# KeyboardMoudle1.net
KiCad netlist of a schematic drawn in Altium Designer
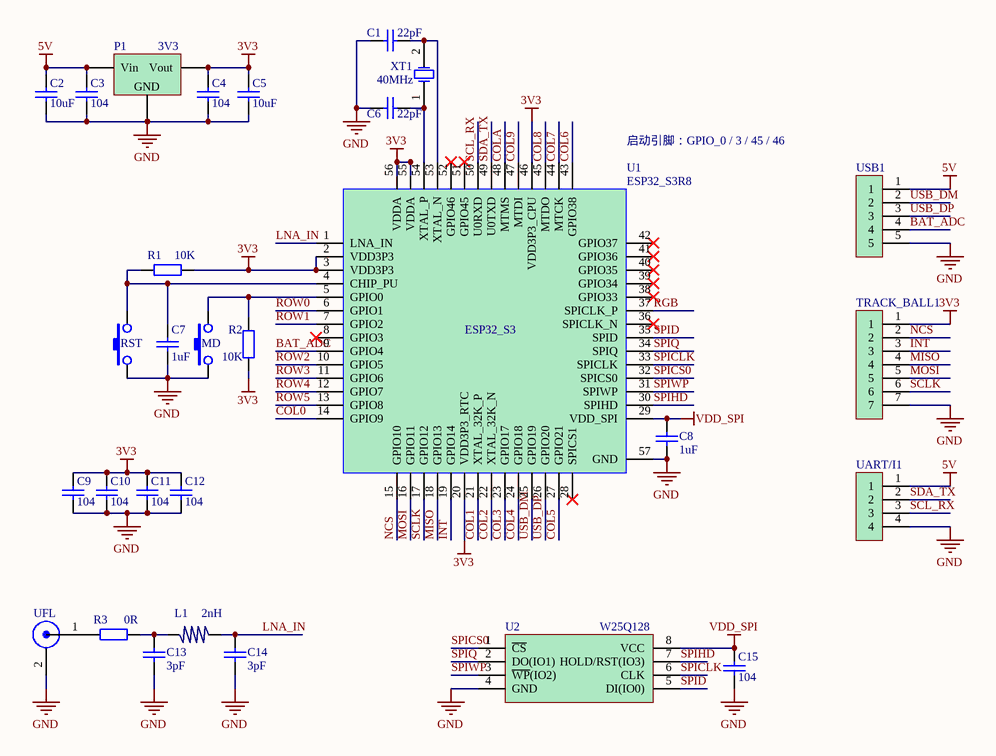
[diagram p0: KeyboardMoudle1.SchDoc]

(export (version "E")
  (design (tool "Eeschema 10.0.6"))
  (components
    (comp (ref "C1")
      (value "22pF")
      (footprint "0603")
      (description "贴片电容 0603")
      (libsource (lib "MT_Device") (part "CAP_0603"))
    )
    (comp (ref "C2")
      (value "10uF")
      (footprint "0603")
      (description "贴片电容 0603")
      (libsource (lib "MT_Device") (part "CAP_0603"))
    )
    (comp (ref "C3")
      (value "104")
      (footprint "0603")
      (description "贴片电容 0603")
      (libsource (lib "MT_Device") (part "CAP_0603"))
    )
    (comp (ref "C4")
      (value "104")
      (footprint "0603")
      (description "贴片电容 0603")
      (libsource (lib "MT_Device") (part "CAP_0603"))
    )
    (comp (ref "C5")
      (value "10uF")
      (footprint "0603")
      (description "贴片电容 0603")
      (libsource (lib "MT_Device") (part "CAP_0603"))
    )
    (comp (ref "C6")
      (value "22pF")
      (footprint "0603")
      (description "贴片电容 0603")
      (libsource (lib "MT_Device") (part "CAP_0603"))
    )
    (comp (ref "C7")
      (value "1uF")
      (footprint "0603")
      (description "贴片电容 0603")
      (libsource (lib "MT_Device") (part "CAP_0603"))
    )
    (comp (ref "C8")
      (value "1uF")
      (footprint "0603")
      (description "贴片电容 0603")
      (libsource (lib "MT_Device") (part "CAP_0603"))
    )
    (comp (ref "C9")
      (value "104")
      (footprint "0603")
      (description "贴片电容 0603")
      (libsource (lib "MT_Device") (part "CAP_0603"))
    )
    (comp (ref "C10")
      (value "104")
      (footprint "0603")
      (description "贴片电容 0603")
      (libsource (lib "MT_Device") (part "CAP_0603"))
    )
    (comp (ref "C11")
      (value "104")
      (footprint "0603")
      (description "贴片电容 0603")
      (libsource (lib "MT_Device") (part "CAP_0603"))
    )
    (comp (ref "C12")
      (value "104")
      (footprint "0603")
      (description "贴片电容 0603")
      (libsource (lib "MT_Device") (part "CAP_0603"))
    )
    (comp (ref "C13")
      (value "3pF")
      (footprint "0603")
      (description "贴片电容 0603")
      (libsource (lib "MT_Device") (part "CAP_0603"))
    )
    (comp (ref "C14")
      (value "3pF")
      (footprint "0603")
      (description "贴片电容 0603")
      (libsource (lib "MT_Device") (part "CAP_0603"))
    )
    (comp (ref "C15")
      (value "104")
      (footprint "0603")
      (description "贴片电容 0603")
      (libsource (lib "MT_Device") (part "CAP_0603"))
    )
    (comp (ref "L1")
      (value "2nH")
      (footprint "0603")
      (description "电感 0603")
      (libsource (lib "MT_Device") (part "L_0603"))
    )
    (comp (ref "MD")
      (value "KEY")
      (footprint "KEY_SMT_4_L")
      (description "卧式贴片按键 2*4*3.5mm")
      (libsource (lib "MT_Device") (part "KEY_SMT_4_L"))
    )
    (comp (ref "P1")
      (value "3V3")
      (footprint "SOT223")
      (description "线性稳压器")
      (libsource (lib "MT_Device") (part "LDO_AMS1117"))
    )
    (comp (ref "R1")
      (value "10K")
      (footprint "R_0603")
      (description "电阻 0603")
      (libsource (lib "") (part "RES_0603_1"))
    )
    (comp (ref "R2")
      (value "10K")
      (footprint "R_0603")
      (description "电阻 0603")
      (libsource (lib "") (part "RES_0603_2"))
    )
    (comp (ref "R3")
      (value "0R")
      (footprint "R_0603")
      (description "电阻 0603")
      (libsource (lib "MT_Device") (part "RES_0603"))
    )
    (comp (ref "RST")
      (value "KEY")
      (footprint "KEY_SMT_4_L")
      (description "卧式贴片按键 2*4*3.5mm")
      (libsource (lib "MT_Device") (part "KEY_SMT_4_L"))
    )
    (comp (ref "TRACK_BALL1")
      (value "SH1.25mm_7P")
      (footprint "SH1.25MM_7P")
      (libsource (lib "MT_Connector") (part "SH1.25mm_7P"))
    )
    (comp (ref "U1")
      (value "ESP32_S3R8")
      (footprint "QFN56")
      (description "ESP32")
      (libsource (lib "MT_Chip") (part "ESP32_S3"))
    )
    (comp (ref "U2")
      (value "W25Q128")
      (footprint "SOIC8-208MIL")
      (description "FLASH")
      (libsource (lib "MT_Chip") (part "W25Q64"))
    )
    (comp (ref "UART/I1")
      (value "SH1.25mm_4P")
      (footprint "SH1.25MM_4P")
      (libsource (lib "MT_Connector") (part "SH1.25mm_4P"))
    )
    (comp (ref "UFL")
      (value "UFL")
      (footprint "IPEX")
      (description "射频接口")
      (libsource (lib "MT_Device") (part "UFL"))
    )
    (comp (ref "USB1")
      (value "SH1.25mm_5P")
      (footprint "SH1.25MM_5P")
      (libsource (lib "MT_Connector") (part "SH1.25mm_5P"))
    )
    (comp (ref "XT1")
      (value "40MHz")
      (footprint "XTAL_5032")
      (description "贴片无源晶振")
      (libsource (lib "MT_Device") (part "XTAL_5032"))
    )
  )
  (nets
    (net (code "1") (name "/BAT_ADC") (class "Default")
      (node (ref "U1") (pin "9") (pinfunction "GPIO4_9") (pintype "passive"))
      (node (ref "USB1") (pin "4") (pinfunction "4_4") (pintype "passive"))
    )
    (net (code "2") (name "/COL0") (class "Default")
      (node (ref "U1") (pin "14") (pinfunction "GPIO9_14") (pintype "passive"))
    )
    (net (code "3") (name "/COL1") (class "Default")
      (node (ref "U1") (pin "21") (pinfunction "XTAL_32K_P_21") (pintype "passive"))
    )
    (net (code "4") (name "/COL2") (class "Default")
      (node (ref "U1") (pin "22") (pinfunction "XTAL_32K_N_22") (pintype "passive"))
    )
    (net (code "5") (name "/COL3") (class "Default")
      (node (ref "U1") (pin "23") (pinfunction "GPIO17_23") (pintype "passive"))
    )
    (net (code "6") (name "/COL4") (class "Default")
      (node (ref "U1") (pin "24") (pinfunction "GPIO18_24") (pintype "passive"))
    )
    (net (code "7") (name "/COL5") (class "Default")
      (node (ref "U1") (pin "27") (pinfunction "GPIO21_27") (pintype "passive"))
    )
    (net (code "8") (name "/COL6") (class "Default")
      (node (ref "U1") (pin "43") (pinfunction "GPIO38_43") (pintype "passive"))
    )
    (net (code "9") (name "/COL7") (class "Default")
      (node (ref "U1") (pin "44") (pinfunction "MTCK_44") (pintype "passive"))
    )
    (net (code "10") (name "/COL8") (class "Default")
      (node (ref "U1") (pin "45") (pinfunction "MTDO_45") (pintype "passive"))
    )
    (net (code "11") (name "/COL9") (class "Default")
      (node (ref "U1") (pin "47") (pinfunction "MTDI_47") (pintype "passive"))
    )
    (net (code "12") (name "/COLA") (class "Default")
      (node (ref "U1") (pin "48") (pinfunction "MTMS_48") (pintype "passive"))
    )
    (net (code "13") (name "/INT") (class "Default")
      (node (ref "TRACK_BALL1") (pin "3") (pinfunction "3_3") (pintype "passive"))
      (node (ref "U1") (pin "19") (pinfunction "GPIO14_19") (pintype "passive"))
    )
    (net (code "14") (name "/LNA_IN") (class "Default")
      (node (ref "C14") (pin "1") (pinfunction "1_1") (pintype "passive"))
      (node (ref "L1") (pin "2") (pintype "passive"))
      (node (ref "U1") (pin "1") (pinfunction "LNA_IN_1") (pintype "passive"))
    )
    (net (code "15") (name "/MISO") (class "Default")
      (node (ref "TRACK_BALL1") (pin "4") (pinfunction "4_4") (pintype "passive"))
      (node (ref "U1") (pin "18") (pinfunction "GPIO13_18") (pintype "passive"))
    )
    (net (code "16") (name "/MOSI") (class "Default")
      (node (ref "TRACK_BALL1") (pin "5") (pinfunction "5_5") (pintype "passive"))
      (node (ref "U1") (pin "16") (pinfunction "GPIO11_16") (pintype "passive"))
    )
    (net (code "17") (name "/NCS") (class "Default")
      (node (ref "TRACK_BALL1") (pin "2") (pinfunction "2_2") (pintype "passive"))
      (node (ref "U1") (pin "15") (pinfunction "GPIO10_15") (pintype "passive"))
    )
    (net (code "18") (name "/RGB") (class "Default")
      (node (ref "U1") (pin "37") (pinfunction "SPICLK_P_37") (pintype "passive"))
    )
    (net (code "19") (name "/ROW0") (class "Default")
      (node (ref "U1") (pin "6") (pinfunction "GPIO1_6") (pintype "passive"))
    )
    (net (code "20") (name "/ROW1") (class "Default")
      (node (ref "U1") (pin "7") (pinfunction "GPIO2_7") (pintype "passive"))
    )
    (net (code "21") (name "/ROW2") (class "Default")
      (node (ref "U1") (pin "10") (pinfunction "GPIO5_10") (pintype "passive"))
    )
    (net (code "22") (name "/ROW3") (class "Default")
      (node (ref "U1") (pin "11") (pinfunction "GPIO6_11") (pintype "passive"))
    )
    (net (code "23") (name "/ROW4") (class "Default")
      (node (ref "U1") (pin "12") (pinfunction "GPIO7_12") (pintype "passive"))
    )
    (net (code "24") (name "/ROW5") (class "Default")
      (node (ref "U1") (pin "13") (pinfunction "GPIO8_13") (pintype "passive"))
    )
    (net (code "25") (name "/SCLK") (class "Default")
      (node (ref "TRACK_BALL1") (pin "6") (pinfunction "6_6") (pintype "passive"))
      (node (ref "U1") (pin "17") (pinfunction "GPIO12_17") (pintype "passive"))
    )
    (net (code "26") (name "/SCL_RX") (class "Default")
      (node (ref "U1") (pin "50") (pinfunction "U0RXD_50") (pintype "passive"))
      (node (ref "UART/I1") (pin "3") (pinfunction "3_3") (pintype "passive"))
    )
    (net (code "27") (name "/SDA_TX") (class "Default")
      (node (ref "U1") (pin "49") (pinfunction "U0TXD_49") (pintype "passive"))
      (node (ref "UART/I1") (pin "2") (pinfunction "2_2") (pintype "passive"))
    )
    (net (code "28") (name "/SPICLK") (class "Default")
      (node (ref "U1") (pin "33") (pinfunction "SPICLK_33") (pintype "passive"))
      (node (ref "U2") (pin "6") (pinfunction "CLK_6") (pintype "passive"))
    )
    (net (code "29") (name "/SPICS0") (class "Default")
      (node (ref "U1") (pin "32") (pinfunction "SPICS0_32") (pintype "passive"))
      (node (ref "U2") (pin "1") (pinfunction "~{CS}_1") (pintype "passive"))
    )
    (net (code "30") (name "/SPID") (class "Default")
      (node (ref "U1") (pin "35") (pinfunction "SPID_35") (pintype "passive"))
      (node (ref "U2") (pin "5") (pinfunction "DI(IO0)_5") (pintype "power_in"))
    )
    (net (code "31") (name "/SPIHD") (class "Default")
      (node (ref "U1") (pin "30") (pinfunction "SPIHD_30") (pintype "passive"))
      (node (ref "U2") (pin "7") (pinfunction "HOLD/RST(IO3)_7") (pintype "power_in"))
    )
    (net (code "32") (name "/SPIQ") (class "Default")
      (node (ref "U1") (pin "34") (pinfunction "SPIQ_34") (pintype "passive"))
      (node (ref "U2") (pin "2") (pinfunction "DO(IO1)_2") (pintype "passive"))
    )
    (net (code "33") (name "/SPIWP") (class "Default")
      (node (ref "U1") (pin "31") (pinfunction "SPIWP_31") (pintype "passive"))
      (node (ref "U2") (pin "3") (pinfunction "~{WP}(IO2)_3") (pintype "passive"))
    )
    (net (code "34") (name "/USB_DM") (class "Default")
      (node (ref "U1") (pin "25") (pinfunction "GPIO19_25") (pintype "passive"))
      (node (ref "USB1") (pin "2") (pinfunction "2_2") (pintype "passive"))
    )
    (net (code "35") (name "/USB_DP") (class "Default")
      (node (ref "U1") (pin "26") (pinfunction "GPIO20_26") (pintype "passive"))
      (node (ref "USB1") (pin "3") (pinfunction "3_3") (pintype "passive"))
    )
    (net (code "36") (name "3V3") (class "Default")
      (node (ref "C10") (pin "2") (pinfunction "2_2") (pintype "passive"))
      (node (ref "C11") (pin "2") (pinfunction "2_2") (pintype "passive"))
      (node (ref "C12") (pin "2") (pinfunction "2_2") (pintype "passive"))
      (node (ref "C4") (pin "2") (pinfunction "2_2") (pintype "passive"))
      (node (ref "C5") (pin "2") (pinfunction "2_2") (pintype "passive"))
      (node (ref "C9") (pin "2") (pinfunction "2_2") (pintype "passive"))
      (node (ref "P1") (pin "2") (pinfunction "Vout_2") (pintype "passive"))
      (node (ref "R1") (pin "1") (pinfunction "1_1") (pintype "passive"))
      (node (ref "R2") (pin "1") (pinfunction "1_1") (pintype "passive"))
      (node (ref "TRACK_BALL1") (pin "1") (pinfunction "1_1") (pintype "passive"))
      (node (ref "U1") (pin "2") (pinfunction "VDD3P3_2") (pintype "passive"))
      (node (ref "U1") (pin "20") (pinfunction "VDD3P3_RTC_20") (pintype "passive"))
      (node (ref "U1") (pin "3") (pinfunction "VDD3P3_3") (pintype "passive"))
      (node (ref "U1") (pin "46") (pinfunction "VDD3P3_CPU_46") (pintype "passive"))
      (node (ref "U1") (pin "55") (pinfunction "VDDA_55") (pintype "passive"))
      (node (ref "U1") (pin "56") (pinfunction "VDDA_56") (pintype "passive"))
    )
    (net (code "37") (name "5V") (class "Default")
      (node (ref "C2") (pin "2") (pinfunction "2_2") (pintype "passive"))
      (node (ref "C3") (pin "2") (pinfunction "2_2") (pintype "passive"))
      (node (ref "P1") (pin "3") (pinfunction "Vin_3") (pintype "passive"))
      (node (ref "UART/I1") (pin "1") (pinfunction "1_1") (pintype "passive"))
      (node (ref "USB1") (pin "1") (pinfunction "1_1") (pintype "passive"))
    )
    (net (code "38") (name "GND") (class "Default")
      (node (ref "C1") (pin "1") (pinfunction "1_1") (pintype "passive"))
      (node (ref "C10") (pin "1") (pinfunction "1_1") (pintype "passive"))
      (node (ref "C11") (pin "1") (pinfunction "1_1") (pintype "passive"))
      (node (ref "C12") (pin "1") (pinfunction "1_1") (pintype "passive"))
      (node (ref "C13") (pin "2") (pinfunction "2_2") (pintype "passive"))
      (node (ref "C14") (pin "2") (pinfunction "2_2") (pintype "passive"))
      (node (ref "C15") (pin "2") (pinfunction "2_2") (pintype "passive"))
      (node (ref "C2") (pin "1") (pinfunction "1_1") (pintype "passive"))
      (node (ref "C3") (pin "1") (pinfunction "1_1") (pintype "passive"))
      (node (ref "C4") (pin "1") (pinfunction "1_1") (pintype "passive"))
      (node (ref "C5") (pin "1") (pinfunction "1_1") (pintype "passive"))
      (node (ref "C6") (pin "2") (pinfunction "2_2") (pintype "passive"))
      (node (ref "C7") (pin "2") (pinfunction "2_2") (pintype "passive"))
      (node (ref "C8") (pin "2") (pinfunction "2_2") (pintype "passive"))
      (node (ref "C9") (pin "1") (pinfunction "1_1") (pintype "passive"))
      (node (ref "MD") (pin "1") (pinfunction "1_1") (pintype "passive"))
      (node (ref "P1") (pin "1") (pinfunction "GND_1") (pintype "passive"))
      (node (ref "RST") (pin "1") (pinfunction "1_1") (pintype "passive"))
      (node (ref "TRACK_BALL1") (pin "7") (pinfunction "7_7") (pintype "passive"))
      (node (ref "U1") (pin "57") (pinfunction "GND_57") (pintype "passive"))
      (node (ref "U2") (pin "4") (pinfunction "GND_4") (pintype "passive"))
      (node (ref "UART/I1") (pin "4") (pinfunction "4_4") (pintype "passive"))
      (node (ref "UFL") (pin "2") (pinfunction "2_2") (pintype "passive"))
      (node (ref "USB1") (pin "5") (pinfunction "5_5") (pintype "passive"))
    )
    (net (code "39") (name "Net-(C13-Pad1)") (class "Default")
      (node (ref "C13") (pin "1") (pinfunction "1_1") (pintype "passive"))
      (node (ref "L1") (pin "1") (pintype "passive"))
      (node (ref "R3") (pin "2") (pinfunction "2_2") (pintype "passive"))
    )
    (net (code "40") (name "Net-(R3-Pad1)") (class "Default")
      (node (ref "R3") (pin "1") (pinfunction "1_1") (pintype "passive"))
      (node (ref "UFL") (pin "1") (pinfunction "1_1") (pintype "passive"))
    )
    (net (code "41") (name "Net-(U1-CHIP_PU)") (class "Default")
      (node (ref "C7") (pin "1") (pinfunction "1_1") (pintype "passive"))
      (node (ref "R1") (pin "2") (pinfunction "2_2") (pintype "passive"))
      (node (ref "RST") (pin "2") (pinfunction "2_2") (pintype "passive"))
      (node (ref "U1") (pin "4") (pinfunction "CHIP_PU_4") (pintype "passive"))
    )
    (net (code "42") (name "Net-(U1-GPIO0)") (class "Default")
      (node (ref "MD") (pin "2") (pinfunction "2_2") (pintype "passive"))
      (node (ref "R2") (pin "2") (pinfunction "2_2") (pintype "passive"))
      (node (ref "U1") (pin "5") (pinfunction "GPIO0_5") (pintype "passive"))
    )
    (net (code "43") (name "Net-(U1-XTAL_N)") (class "Default")
      (node (ref "C1") (pin "2") (pinfunction "2_2") (pintype "passive"))
      (node (ref "U1") (pin "53") (pinfunction "XTAL_N_53") (pintype "passive"))
      (node (ref "XT1") (pin "2") (pinfunction "OSC2_2") (pintype "passive"))
    )
    (net (code "44") (name "Net-(U1-XTAL_P)") (class "Default")
      (node (ref "C6") (pin "1") (pinfunction "1_1") (pintype "passive"))
      (node (ref "U1") (pin "54") (pinfunction "XTAL_P_54") (pintype "passive"))
      (node (ref "XT1") (pin "1") (pinfunction "OSC1_1") (pintype "passive"))
    )
    (net (code "45") (name "VDD_SPI") (class "Default")
      (node (ref "C15") (pin "1") (pinfunction "1_1") (pintype "passive"))
      (node (ref "C8") (pin "1") (pinfunction "1_1") (pintype "passive"))
      (node (ref "U1") (pin "29") (pinfunction "VDD_SPI_29") (pintype "passive"))
      (node (ref "U2") (pin "8") (pinfunction "VCC_8") (pintype "passive"))
    )
    (net (code "46") (name "unconnected-(U1-GPIO3-Pad8)") (class "Default")
      (node (ref "U1") (pin "8") (pinfunction "GPIO3_8") (pintype "passive+no_connect"))
    )
    (net (code "47") (name "unconnected-(U1-GPIO33-Pad38)") (class "Default")
      (node (ref "U1") (pin "38") (pinfunction "GPIO33_38") (pintype "passive+no_connect"))
    )
    (net (code "48") (name "unconnected-(U1-GPIO34-Pad39)") (class "Default")
      (node (ref "U1") (pin "39") (pinfunction "GPIO34_39") (pintype "passive+no_connect"))
    )
    (net (code "49") (name "unconnected-(U1-GPIO35-Pad40)") (class "Default")
      (node (ref "U1") (pin "40") (pinfunction "GPIO35_40") (pintype "passive+no_connect"))
    )
    (net (code "50") (name "unconnected-(U1-GPIO36-Pad41)") (class "Default")
      (node (ref "U1") (pin "41") (pinfunction "GPIO36_41") (pintype "passive+no_connect"))
    )
    (net (code "51") (name "unconnected-(U1-GPIO37-Pad42)") (class "Default")
      (node (ref "U1") (pin "42") (pinfunction "GPIO37_42") (pintype "passive+no_connect"))
    )
    (net (code "52") (name "unconnected-(U1-GPIO45-Pad51)") (class "Default")
      (node (ref "U1") (pin "51") (pinfunction "GPIO45_51") (pintype "passive+no_connect"))
    )
    (net (code "53") (name "unconnected-(U1-GPIO46-Pad52)") (class "Default")
      (node (ref "U1") (pin "52") (pinfunction "GPIO46_52") (pintype "passive+no_connect"))
    )
    (net (code "54") (name "unconnected-(U1-SPICLK_N-Pad36)") (class "Default")
      (node (ref "U1") (pin "36") (pinfunction "SPICLK_N_36") (pintype "passive+no_connect"))
    )
    (net (code "55") (name "unconnected-(U1-SPICS1-Pad28)") (class "Default")
      (node (ref "U1") (pin "28") (pinfunction "SPICS1_28") (pintype "passive+no_connect"))
    )
  )
)
